# Sensor.net
KiCad netlist of a schematic drawn in EAGLE
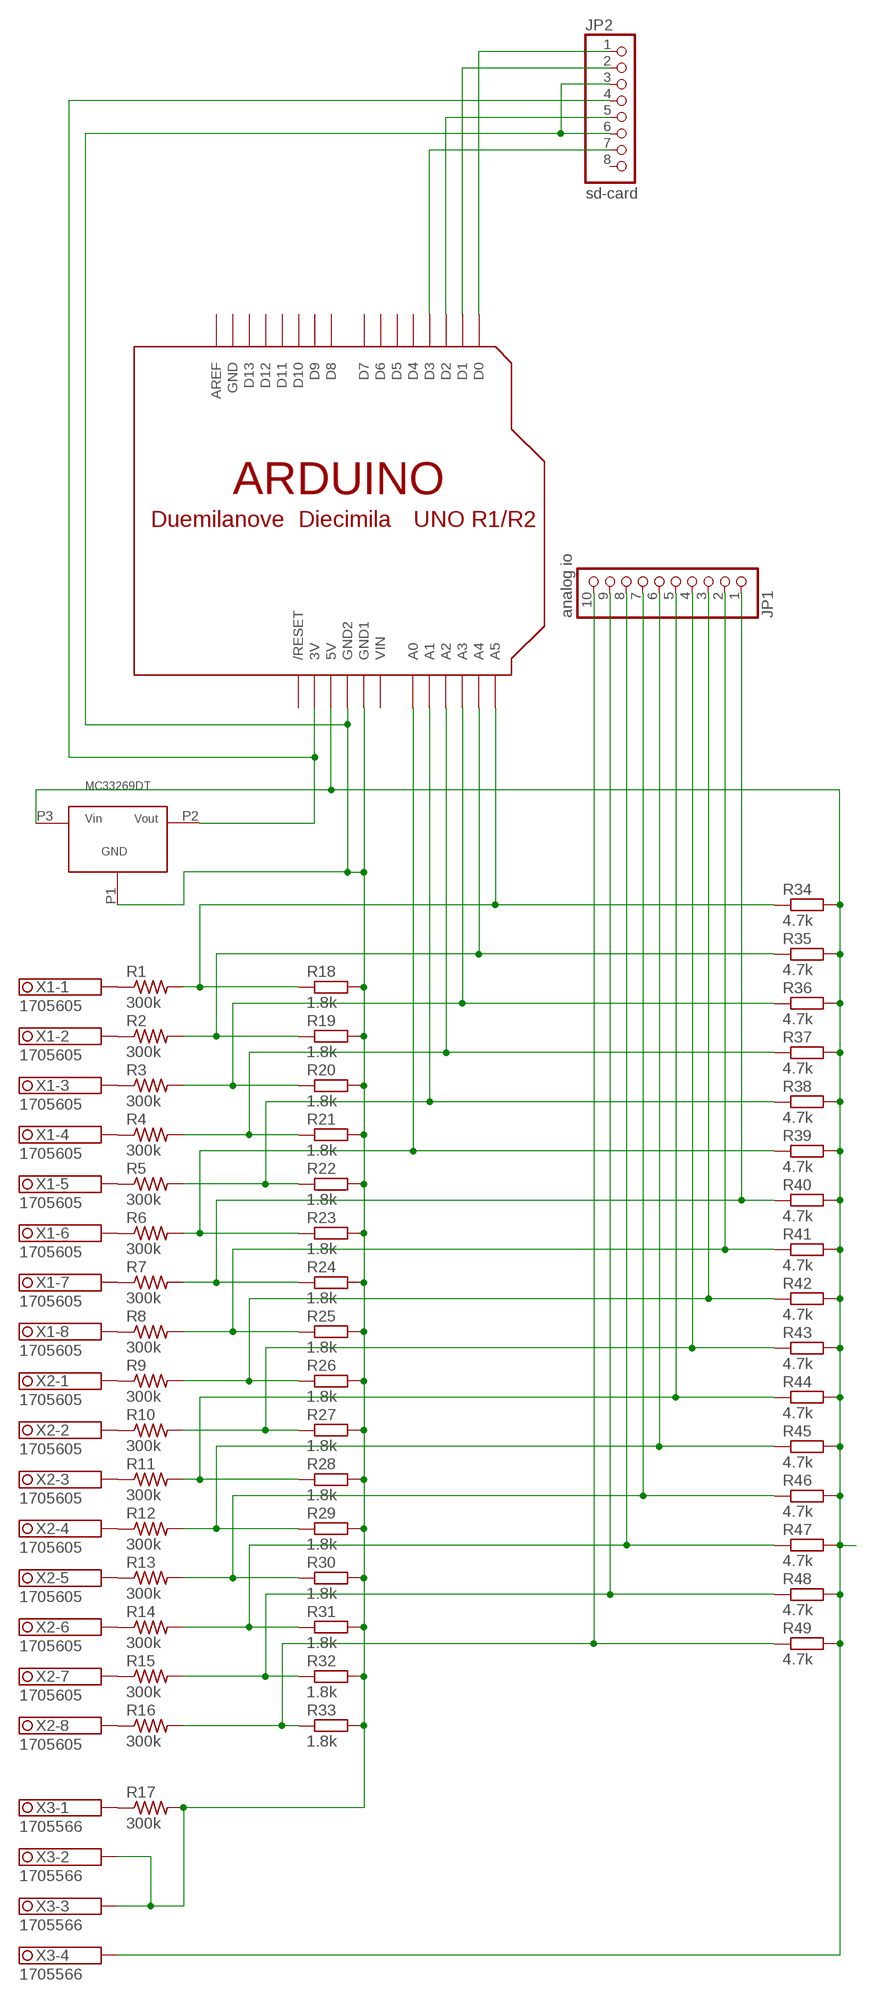
[diagram p0: schematic, sheet 1]

(export (version "E")
  (design (tool "Eeschema 10.0.6"))
  (components
    (comp (ref "JP1")
      (value "analog io")
      (footprint "eagle-import:1X10")
      (libsource (lib "eagle-import") (part "PINHD-1X10"))
    )
    (comp (ref "JP2")
      (value "sd-card")
      (footprint "eagle-import:1X08")
      (libsource (lib "eagle-import") (part "PINHD-1X8"))
    )
    (comp (ref "R1")
      (value "300k")
      (footprint "eagle-import:0207_15")
      (libsource (lib "eagle-import") (part "R-US_0207/15"))
    )
    (comp (ref "R2")
      (value "300k")
      (footprint "eagle-import:0207_15")
      (libsource (lib "eagle-import") (part "R-US_0207/15"))
    )
    (comp (ref "R3")
      (value "300k")
      (footprint "eagle-import:0207_15")
      (libsource (lib "eagle-import") (part "R-US_0207/15"))
    )
    (comp (ref "R4")
      (value "300k")
      (footprint "eagle-import:0207_15")
      (libsource (lib "eagle-import") (part "R-US_0207/15"))
    )
    (comp (ref "R5")
      (value "300k")
      (footprint "eagle-import:0207_15")
      (libsource (lib "eagle-import") (part "R-US_0207/15"))
    )
    (comp (ref "R6")
      (value "300k")
      (footprint "eagle-import:0207_15")
      (libsource (lib "eagle-import") (part "R-US_0207/15"))
    )
    (comp (ref "R7")
      (value "300k")
      (footprint "eagle-import:0207_15")
      (libsource (lib "eagle-import") (part "R-US_0207/15"))
    )
    (comp (ref "R8")
      (value "300k")
      (footprint "eagle-import:0207_15")
      (libsource (lib "eagle-import") (part "R-US_0207/15"))
    )
    (comp (ref "R9")
      (value "300k")
      (footprint "eagle-import:0207_15")
      (libsource (lib "eagle-import") (part "R-US_0207/15"))
    )
    (comp (ref "R10")
      (value "300k")
      (footprint "eagle-import:0207_15")
      (libsource (lib "eagle-import") (part "R-US_0207/15"))
    )
    (comp (ref "R11")
      (value "300k")
      (footprint "eagle-import:0207_15")
      (libsource (lib "eagle-import") (part "R-US_0207/15"))
    )
    (comp (ref "R12")
      (value "300k")
      (footprint "eagle-import:0207_15")
      (libsource (lib "eagle-import") (part "R-US_0207/15"))
    )
    (comp (ref "R13")
      (value "300k")
      (footprint "eagle-import:0207_15")
      (libsource (lib "eagle-import") (part "R-US_0207/15"))
    )
    (comp (ref "R14")
      (value "300k")
      (footprint "eagle-import:0207_15")
      (libsource (lib "eagle-import") (part "R-US_0207/15"))
    )
    (comp (ref "R15")
      (value "300k")
      (footprint "eagle-import:0207_15")
      (libsource (lib "eagle-import") (part "R-US_0207/15"))
    )
    (comp (ref "R16")
      (value "300k")
      (footprint "eagle-import:0207_15")
      (libsource (lib "eagle-import") (part "R-US_0207/15"))
    )
    (comp (ref "R17")
      (value "300k")
      (footprint "eagle-import:0207_15")
      (libsource (lib "eagle-import") (part "R-US_0207/15"))
    )
    (comp (ref "R18")
      (value "1.8k")
      (footprint "eagle-import:R1206")
      (libsource (lib "eagle-import") (part "R-EU_R1206"))
    )
    (comp (ref "R19")
      (value "1.8k")
      (footprint "eagle-import:R1206")
      (libsource (lib "eagle-import") (part "R-EU_R1206"))
    )
    (comp (ref "R20")
      (value "1.8k")
      (footprint "eagle-import:R1206")
      (libsource (lib "eagle-import") (part "R-EU_R1206"))
    )
    (comp (ref "R21")
      (value "1.8k")
      (footprint "eagle-import:R1206")
      (libsource (lib "eagle-import") (part "R-EU_R1206"))
    )
    (comp (ref "R22")
      (value "1.8k")
      (footprint "eagle-import:R1206")
      (libsource (lib "eagle-import") (part "R-EU_R1206"))
    )
    (comp (ref "R23")
      (value "1.8k")
      (footprint "eagle-import:R1206")
      (libsource (lib "eagle-import") (part "R-EU_R1206"))
    )
    (comp (ref "R24")
      (value "1.8k")
      (footprint "eagle-import:R1206")
      (libsource (lib "eagle-import") (part "R-EU_R1206"))
    )
    (comp (ref "R25")
      (value "1.8k")
      (footprint "eagle-import:R1206")
      (libsource (lib "eagle-import") (part "R-EU_R1206"))
    )
    (comp (ref "R26")
      (value "1.8k")
      (footprint "eagle-import:R1206")
      (libsource (lib "eagle-import") (part "R-EU_R1206"))
    )
    (comp (ref "R27")
      (value "1.8k")
      (footprint "eagle-import:R1206")
      (libsource (lib "eagle-import") (part "R-EU_R1206"))
    )
    (comp (ref "R28")
      (value "1.8k")
      (footprint "eagle-import:R1206")
      (libsource (lib "eagle-import") (part "R-EU_R1206"))
    )
    (comp (ref "R29")
      (value "1.8k")
      (footprint "eagle-import:R1206")
      (libsource (lib "eagle-import") (part "R-EU_R1206"))
    )
    (comp (ref "R30")
      (value "1.8k")
      (footprint "eagle-import:R1206")
      (libsource (lib "eagle-import") (part "R-EU_R1206"))
    )
    (comp (ref "R31")
      (value "1.8k")
      (footprint "eagle-import:R1206")
      (libsource (lib "eagle-import") (part "R-EU_R1206"))
    )
    (comp (ref "R32")
      (value "1.8k")
      (footprint "eagle-import:R1206")
      (libsource (lib "eagle-import") (part "R-EU_R1206"))
    )
    (comp (ref "R33")
      (value "1.8k")
      (footprint "eagle-import:R1206")
      (libsource (lib "eagle-import") (part "R-EU_R1206"))
    )
    (comp (ref "R34")
      (value "4.7k")
      (footprint "eagle-import:R1206")
      (libsource (lib "eagle-import") (part "R-EU_R1206"))
    )
    (comp (ref "R35")
      (value "4.7k")
      (footprint "eagle-import:R1206")
      (libsource (lib "eagle-import") (part "R-EU_R1206"))
    )
    (comp (ref "R36")
      (value "4.7k")
      (footprint "eagle-import:R1206")
      (libsource (lib "eagle-import") (part "R-EU_R1206"))
    )
    (comp (ref "R37")
      (value "4.7k")
      (footprint "eagle-import:R1206")
      (libsource (lib "eagle-import") (part "R-EU_R1206"))
    )
    (comp (ref "R38")
      (value "4.7k")
      (footprint "eagle-import:R1206")
      (libsource (lib "eagle-import") (part "R-EU_R1206"))
    )
    (comp (ref "R39")
      (value "4.7k")
      (footprint "eagle-import:R1206")
      (libsource (lib "eagle-import") (part "R-EU_R1206"))
    )
    (comp (ref "R40")
      (value "4.7k")
      (footprint "eagle-import:R1206")
      (libsource (lib "eagle-import") (part "R-EU_R1206"))
    )
    (comp (ref "R41")
      (value "4.7k")
      (footprint "eagle-import:R1206")
      (libsource (lib "eagle-import") (part "R-EU_R1206"))
    )
    (comp (ref "R42")
      (value "4.7k")
      (footprint "eagle-import:R1206")
      (libsource (lib "eagle-import") (part "R-EU_R1206"))
    )
    (comp (ref "R43")
      (value "4.7k")
      (footprint "eagle-import:R1206")
      (libsource (lib "eagle-import") (part "R-EU_R1206"))
    )
    (comp (ref "R44")
      (value "4.7k")
      (footprint "eagle-import:R1206")
      (libsource (lib "eagle-import") (part "R-EU_R1206"))
    )
    (comp (ref "R45")
      (value "4.7k")
      (footprint "eagle-import:R1206")
      (libsource (lib "eagle-import") (part "R-EU_R1206"))
    )
    (comp (ref "R46")
      (value "4.7k")
      (footprint "eagle-import:R1206")
      (libsource (lib "eagle-import") (part "R-EU_R1206"))
    )
    (comp (ref "R47")
      (value "4.7k")
      (footprint "eagle-import:R1206")
      (libsource (lib "eagle-import") (part "R-EU_R1206"))
    )
    (comp (ref "R48")
      (value "4.7k")
      (footprint "eagle-import:R1206")
      (libsource (lib "eagle-import") (part "R-EU_R1206"))
    )
    (comp (ref "R49")
      (value "4.7k")
      (footprint "eagle-import:R1206")
      (libsource (lib "eagle-import") (part "R-EU_R1206"))
    )
    (comp (ref "U$1")
      (value "MC33269DT")
      (footprint "eagle-import:MC33269DT")
      (libsource (lib "eagle-import") (part "MC33269DT"))
    )
    (comp (ref "U$2")
      (value "ARDUINOUNO")
      (footprint "eagle-import:ARDUINO")
      (libsource (lib "eagle-import") (part "ARDUINOUNO"))
    )
    (comp (ref "X1")
      (value "1705605")
      (footprint "eagle-import:1705605")
      (libsource (lib "eagle-import") (part "1705605"))
    )
    (comp (ref "X2")
      (value "1705605")
      (footprint "eagle-import:1705605")
      (libsource (lib "eagle-import") (part "1705605"))
    )
    (comp (ref "X3")
      (value "1705566")
      (footprint "eagle-import:1705566")
      (libsource (lib "eagle-import") (part "1705566"))
    )
  )
  (nets
    (net (code "1") (name "/GND") (class "Default")
      (node (ref "U$2") (pin "GND") (pinfunction "GND_GND") (pintype "power_in"))
    )
    (net (code "2") (name "/VIN") (class "Default")
      (node (ref "U$2") (pin "VIN") (pinfunction "VIN_VIN") (pintype "power_in"))
    )
    (net (code "3") (name "Net-(JP1-Pad1)") (class "Default")
      (node (ref "JP1") (pin "1") (pinfunction "1_1") (pintype "passive"))
      (node (ref "R24") (pin "1") (pinfunction "1_1") (pintype "passive"))
      (node (ref "R40") (pin "1") (pinfunction "1_1") (pintype "passive"))
      (node (ref "R7") (pin "2") (pinfunction "2_2") (pintype "passive"))
    )
    (net (code "4") (name "Net-(JP1-Pad2)") (class "Default")
      (node (ref "JP1") (pin "2") (pinfunction "2_2") (pintype "passive"))
      (node (ref "R25") (pin "1") (pinfunction "1_1") (pintype "passive"))
      (node (ref "R41") (pin "1") (pinfunction "1_1") (pintype "passive"))
      (node (ref "R8") (pin "2") (pinfunction "2_2") (pintype "passive"))
    )
    (net (code "5") (name "Net-(JP1-Pad3)") (class "Default")
      (node (ref "JP1") (pin "3") (pinfunction "3_3") (pintype "passive"))
      (node (ref "R26") (pin "1") (pinfunction "1_1") (pintype "passive"))
      (node (ref "R42") (pin "1") (pinfunction "1_1") (pintype "passive"))
      (node (ref "R9") (pin "2") (pinfunction "2_2") (pintype "passive"))
    )
    (net (code "6") (name "Net-(JP1-Pad4)") (class "Default")
      (node (ref "JP1") (pin "4") (pinfunction "4_4") (pintype "passive"))
      (node (ref "R10") (pin "2") (pinfunction "2_2") (pintype "passive"))
      (node (ref "R27") (pin "1") (pinfunction "1_1") (pintype "passive"))
      (node (ref "R43") (pin "1") (pinfunction "1_1") (pintype "passive"))
    )
    (net (code "7") (name "Net-(JP1-Pad5)") (class "Default")
      (node (ref "JP1") (pin "5") (pinfunction "5_5") (pintype "passive"))
      (node (ref "R11") (pin "2") (pinfunction "2_2") (pintype "passive"))
      (node (ref "R28") (pin "1") (pinfunction "1_1") (pintype "passive"))
      (node (ref "R44") (pin "1") (pinfunction "1_1") (pintype "passive"))
    )
    (net (code "8") (name "Net-(JP1-Pad6)") (class "Default")
      (node (ref "JP1") (pin "6") (pinfunction "6_6") (pintype "passive"))
      (node (ref "R12") (pin "2") (pinfunction "2_2") (pintype "passive"))
      (node (ref "R29") (pin "1") (pinfunction "1_1") (pintype "passive"))
      (node (ref "R45") (pin "1") (pinfunction "1_1") (pintype "passive"))
    )
    (net (code "9") (name "Net-(JP1-Pad7)") (class "Default")
      (node (ref "JP1") (pin "7") (pinfunction "7_7") (pintype "passive"))
      (node (ref "R13") (pin "2") (pinfunction "2_2") (pintype "passive"))
      (node (ref "R30") (pin "1") (pinfunction "1_1") (pintype "passive"))
      (node (ref "R46") (pin "1") (pinfunction "1_1") (pintype "passive"))
    )
    (net (code "10") (name "Net-(JP1-Pad8)") (class "Default")
      (node (ref "JP1") (pin "8") (pinfunction "8_8") (pintype "passive"))
      (node (ref "R14") (pin "2") (pinfunction "2_2") (pintype "passive"))
      (node (ref "R31") (pin "1") (pinfunction "1_1") (pintype "passive"))
      (node (ref "R47") (pin "1") (pinfunction "1_1") (pintype "passive"))
    )
    (net (code "11") (name "Net-(JP1-Pad9)") (class "Default")
      (node (ref "JP1") (pin "9") (pinfunction "9_9") (pintype "passive"))
      (node (ref "R15") (pin "2") (pinfunction "2_2") (pintype "passive"))
      (node (ref "R32") (pin "1") (pinfunction "1_1") (pintype "passive"))
      (node (ref "R48") (pin "1") (pinfunction "1_1") (pintype "passive"))
    )
    (net (code "12") (name "Net-(JP1-Pad10)") (class "Default")
      (node (ref "JP1") (pin "10") (pinfunction "10_10") (pintype "passive"))
      (node (ref "R16") (pin "2") (pinfunction "2_2") (pintype "passive"))
      (node (ref "R33") (pin "1") (pinfunction "1_1") (pintype "passive"))
      (node (ref "R49") (pin "1") (pinfunction "1_1") (pintype "passive"))
    )
    (net (code "13") (name "Net-(JP2-Pad1)") (class "Default")
      (node (ref "JP2") (pin "1") (pinfunction "1_1") (pintype "passive"))
      (node (ref "U$2") (pin "D0") (pinfunction "D0_D0") (pintype "bidirectional"))
    )
    (net (code "14") (name "Net-(JP2-Pad2)") (class "Default")
      (node (ref "JP2") (pin "2") (pinfunction "2_2") (pintype "passive"))
      (node (ref "U$2") (pin "D1") (pinfunction "D1_D1") (pintype "bidirectional"))
    )
    (net (code "15") (name "Net-(JP2-Pad5)") (class "Default")
      (node (ref "JP2") (pin "5") (pinfunction "5_5") (pintype "passive"))
      (node (ref "U$2") (pin "D2") (pinfunction "D2_D2") (pintype "bidirectional"))
    )
    (net (code "16") (name "Net-(JP2-Pad7)") (class "Default")
      (node (ref "JP2") (pin "7") (pinfunction "7_7") (pintype "passive"))
      (node (ref "U$2") (pin "D3") (pinfunction "D3_D3") (pintype "bidirectional"))
    )
    (net (code "17") (name "Net-(R1-Pad1)") (class "Default")
      (node (ref "R1") (pin "1") (pinfunction "1_1") (pintype "passive"))
      (node (ref "X1") (pin "1.1") (pinfunction "1A_1.1") (pintype "passive"))
      (node (ref "X1") (pin "1.2") (pinfunction "1A_1.2") (pintype "passive"))
    )
    (net (code "18") (name "Net-(R1-Pad2)") (class "Default")
      (node (ref "R1") (pin "2") (pinfunction "2_2") (pintype "passive"))
      (node (ref "R18") (pin "1") (pinfunction "1_1") (pintype "passive"))
      (node (ref "R34") (pin "1") (pinfunction "1_1") (pintype "passive"))
      (node (ref "U$2") (pin "A5") (pinfunction "A5_A5") (pintype "bidirectional"))
    )
    (net (code "19") (name "Net-(R2-Pad1)") (class "Default")
      (node (ref "R2") (pin "1") (pinfunction "1_1") (pintype "passive"))
      (node (ref "X1") (pin "2.1") (pinfunction "1A_2.1") (pintype "passive"))
      (node (ref "X1") (pin "2.2") (pinfunction "1A_2.2") (pintype "passive"))
    )
    (net (code "20") (name "Net-(R3-Pad1)") (class "Default")
      (node (ref "R3") (pin "1") (pinfunction "1_1") (pintype "passive"))
      (node (ref "X1") (pin "3.1") (pinfunction "1A_3.1") (pintype "passive"))
      (node (ref "X1") (pin "3.2") (pinfunction "1A_3.2") (pintype "passive"))
    )
    (net (code "21") (name "Net-(R4-Pad1)") (class "Default")
      (node (ref "R4") (pin "1") (pinfunction "1_1") (pintype "passive"))
      (node (ref "X1") (pin "4.1") (pinfunction "1A_4.1") (pintype "passive"))
      (node (ref "X1") (pin "4.2") (pinfunction "1A_4.2") (pintype "passive"))
    )
    (net (code "22") (name "Net-(R5-Pad1)") (class "Default")
      (node (ref "R5") (pin "1") (pinfunction "1_1") (pintype "passive"))
      (node (ref "X1") (pin "5.1") (pinfunction "1A_5.1") (pintype "passive"))
      (node (ref "X1") (pin "5.2") (pinfunction "1A_5.2") (pintype "passive"))
    )
    (net (code "23") (name "Net-(R6-Pad1)") (class "Default")
      (node (ref "R6") (pin "1") (pinfunction "1_1") (pintype "passive"))
      (node (ref "X1") (pin "6.1") (pinfunction "1A_6.1") (pintype "passive"))
      (node (ref "X1") (pin "6.2") (pinfunction "1A_6.2") (pintype "passive"))
    )
    (net (code "24") (name "Net-(R7-Pad1)") (class "Default")
      (node (ref "R7") (pin "1") (pinfunction "1_1") (pintype "passive"))
      (node (ref "X1") (pin "7.1") (pinfunction "1A_7.1") (pintype "passive"))
      (node (ref "X1") (pin "7.2") (pinfunction "1A_7.2") (pintype "passive"))
    )
    (net (code "25") (name "Net-(R8-Pad1)") (class "Default")
      (node (ref "R8") (pin "1") (pinfunction "1_1") (pintype "passive"))
      (node (ref "X1") (pin "8.1") (pinfunction "1A_8.1") (pintype "passive"))
      (node (ref "X1") (pin "8.2") (pinfunction "1A_8.2") (pintype "passive"))
    )
    (net (code "26") (name "Net-(R9-Pad1)") (class "Default")
      (node (ref "R9") (pin "1") (pinfunction "1_1") (pintype "passive"))
      (node (ref "X2") (pin "1.1") (pinfunction "1A_1.1") (pintype "passive"))
      (node (ref "X2") (pin "1.2") (pinfunction "1A_1.2") (pintype "passive"))
    )
    (net (code "27") (name "Net-(R10-Pad1)") (class "Default")
      (node (ref "R10") (pin "1") (pinfunction "1_1") (pintype "passive"))
      (node (ref "X2") (pin "2.1") (pinfunction "1A_2.1") (pintype "passive"))
      (node (ref "X2") (pin "2.2") (pinfunction "1A_2.2") (pintype "passive"))
    )
    (net (code "28") (name "Net-(R11-Pad1)") (class "Default")
      (node (ref "R11") (pin "1") (pinfunction "1_1") (pintype "passive"))
      (node (ref "X2") (pin "3.1") (pinfunction "1A_3.1") (pintype "passive"))
      (node (ref "X2") (pin "3.2") (pinfunction "1A_3.2") (pintype "passive"))
    )
    (net (code "29") (name "Net-(R12-Pad1)") (class "Default")
      (node (ref "R12") (pin "1") (pinfunction "1_1") (pintype "passive"))
      (node (ref "X2") (pin "4.1") (pinfunction "1A_4.1") (pintype "passive"))
      (node (ref "X2") (pin "4.2") (pinfunction "1A_4.2") (pintype "passive"))
    )
    (net (code "30") (name "Net-(R13-Pad1)") (class "Default")
      (node (ref "R13") (pin "1") (pinfunction "1_1") (pintype "passive"))
      (node (ref "X2") (pin "5.1") (pinfunction "1A_5.1") (pintype "passive"))
      (node (ref "X2") (pin "5.2") (pinfunction "1A_5.2") (pintype "passive"))
    )
    (net (code "31") (name "Net-(R14-Pad1)") (class "Default")
      (node (ref "R14") (pin "1") (pinfunction "1_1") (pintype "passive"))
      (node (ref "X2") (pin "6.1") (pinfunction "1A_6.1") (pintype "passive"))
      (node (ref "X2") (pin "6.2") (pinfunction "1A_6.2") (pintype "passive"))
    )
    (net (code "32") (name "Net-(R15-Pad1)") (class "Default")
      (node (ref "R15") (pin "1") (pinfunction "1_1") (pintype "passive"))
      (node (ref "X2") (pin "7.1") (pinfunction "1A_7.1") (pintype "passive"))
      (node (ref "X2") (pin "7.2") (pinfunction "1A_7.2") (pintype "passive"))
    )
    (net (code "33") (name "Net-(R16-Pad1)") (class "Default")
      (node (ref "R16") (pin "1") (pinfunction "1_1") (pintype "passive"))
      (node (ref "X2") (pin "8.1") (pinfunction "1A_8.1") (pintype "passive"))
      (node (ref "X2") (pin "8.2") (pinfunction "1A_8.2") (pintype "passive"))
    )
    (net (code "34") (name "Net-(R17-Pad1)") (class "Default")
      (node (ref "R17") (pin "1") (pinfunction "1_1") (pintype "passive"))
      (node (ref "X3") (pin "1.1") (pinfunction "1A_1.1") (pintype "passive"))
      (node (ref "X3") (pin "1.2") (pinfunction "1A_1.2") (pintype "passive"))
    )
    (net (code "35") (name "Net-(R19-Pad1)") (class "Default")
      (node (ref "R19") (pin "1") (pinfunction "1_1") (pintype "passive"))
      (node (ref "R2") (pin "2") (pinfunction "2_2") (pintype "passive"))
      (node (ref "R35") (pin "1") (pinfunction "1_1") (pintype "passive"))
      (node (ref "U$2") (pin "A4") (pinfunction "A4_A4") (pintype "bidirectional"))
    )
    (net (code "36") (name "Net-(R20-Pad1)") (class "Default")
      (node (ref "R20") (pin "1") (pinfunction "1_1") (pintype "passive"))
      (node (ref "R3") (pin "2") (pinfunction "2_2") (pintype "passive"))
      (node (ref "R36") (pin "1") (pinfunction "1_1") (pintype "passive"))
      (node (ref "U$2") (pin "A3") (pinfunction "A3_A3") (pintype "bidirectional"))
    )
    (net (code "37") (name "Net-(R21-Pad1)") (class "Default")
      (node (ref "R21") (pin "1") (pinfunction "1_1") (pintype "passive"))
      (node (ref "R37") (pin "1") (pinfunction "1_1") (pintype "passive"))
      (node (ref "R4") (pin "2") (pinfunction "2_2") (pintype "passive"))
      (node (ref "U$2") (pin "A2") (pinfunction "A2_A2") (pintype "bidirectional"))
    )
    (net (code "38") (name "Net-(R22-Pad1)") (class "Default")
      (node (ref "R22") (pin "1") (pinfunction "1_1") (pintype "passive"))
      (node (ref "R38") (pin "1") (pinfunction "1_1") (pintype "passive"))
      (node (ref "R5") (pin "2") (pinfunction "2_2") (pintype "passive"))
      (node (ref "U$2") (pin "A1") (pinfunction "A1_A1") (pintype "bidirectional"))
    )
    (net (code "39") (name "Net-(R23-Pad1)") (class "Default")
      (node (ref "R23") (pin "1") (pinfunction "1_1") (pintype "passive"))
      (node (ref "R39") (pin "1") (pinfunction "1_1") (pintype "passive"))
      (node (ref "R6") (pin "2") (pinfunction "2_2") (pintype "passive"))
      (node (ref "U$2") (pin "A0") (pinfunction "A0_A0") (pintype "bidirectional"))
    )
    (net (code "40") (name "Net-(U$1-GND)") (class "Default")
      (node (ref "JP2") (pin "3") (pinfunction "3_3") (pintype "passive"))
      (node (ref "JP2") (pin "6") (pinfunction "6_6") (pintype "passive"))
      (node (ref "R17") (pin "2") (pinfunction "2_2") (pintype "passive"))
      (node (ref "R18") (pin "2") (pinfunction "2_2") (pintype "passive"))
      (node (ref "R19") (pin "2") (pinfunction "2_2") (pintype "passive"))
      (node (ref "R20") (pin "2") (pinfunction "2_2") (pintype "passive"))
      (node (ref "R21") (pin "2") (pinfunction "2_2") (pintype "passive"))
      (node (ref "R22") (pin "2") (pinfunction "2_2") (pintype "passive"))
      (node (ref "R23") (pin "2") (pinfunction "2_2") (pintype "passive"))
      (node (ref "R24") (pin "2") (pinfunction "2_2") (pintype "passive"))
      (node (ref "R25") (pin "2") (pinfunction "2_2") (pintype "passive"))
      (node (ref "R26") (pin "2") (pinfunction "2_2") (pintype "passive"))
      (node (ref "R27") (pin "2") (pinfunction "2_2") (pintype "passive"))
      (node (ref "R28") (pin "2") (pinfunction "2_2") (pintype "passive"))
      (node (ref "R29") (pin "2") (pinfunction "2_2") (pintype "passive"))
      (node (ref "R30") (pin "2") (pinfunction "2_2") (pintype "passive"))
      (node (ref "R31") (pin "2") (pinfunction "2_2") (pintype "passive"))
      (node (ref "R32") (pin "2") (pinfunction "2_2") (pintype "passive"))
      (node (ref "R33") (pin "2") (pinfunction "2_2") (pintype "passive"))
      (node (ref "U$1") (pin "P1") (pinfunction "GND_P1") (pintype "power_in"))
      (node (ref "U$2") (pin "GND1") (pinfunction "GND1_GND1") (pintype "power_in"))
      (node (ref "U$2") (pin "GND2") (pinfunction "GND2_GND2") (pintype "power_in"))
      (node (ref "X3") (pin "2.1") (pinfunction "1A_2.1") (pintype "passive"))
      (node (ref "X3") (pin "2.2") (pinfunction "1A_2.2") (pintype "passive"))
      (node (ref "X3") (pin "3.1") (pinfunction "1A_3.1") (pintype "passive"))
      (node (ref "X3") (pin "3.2") (pinfunction "1A_3.2") (pintype "passive"))
    )
    (net (code "41") (name "Net-(U$1-VIN)") (class "Default")
      (node (ref "R34") (pin "2") (pinfunction "2_2") (pintype "passive"))
      (node (ref "R35") (pin "2") (pinfunction "2_2") (pintype "passive"))
      (node (ref "R36") (pin "2") (pinfunction "2_2") (pintype "passive"))
      (node (ref "R37") (pin "2") (pinfunction "2_2") (pintype "passive"))
      (node (ref "R38") (pin "2") (pinfunction "2_2") (pintype "passive"))
      (node (ref "R39") (pin "2") (pinfunction "2_2") (pintype "passive"))
      (node (ref "R40") (pin "2") (pinfunction "2_2") (pintype "passive"))
      (node (ref "R41") (pin "2") (pinfunction "2_2") (pintype "passive"))
      (node (ref "R42") (pin "2") (pinfunction "2_2") (pintype "passive"))
      (node (ref "R43") (pin "2") (pinfunction "2_2") (pintype "passive"))
      (node (ref "R44") (pin "2") (pinfunction "2_2") (pintype "passive"))
      (node (ref "R45") (pin "2") (pinfunction "2_2") (pintype "passive"))
      (node (ref "R46") (pin "2") (pinfunction "2_2") (pintype "passive"))
      (node (ref "R47") (pin "2") (pinfunction "2_2") (pintype "passive"))
      (node (ref "R48") (pin "2") (pinfunction "2_2") (pintype "passive"))
      (node (ref "R49") (pin "2") (pinfunction "2_2") (pintype "passive"))
      (node (ref "U$1") (pin "P3") (pinfunction "VIN_P3") (pintype "input"))
      (node (ref "U$2") (pin "5V") (pinfunction "5V_5V") (pintype "power_in"))
      (node (ref "X3") (pin "4.1") (pinfunction "1A_4.1") (pintype "passive"))
      (node (ref "X3") (pin "4.2") (pinfunction "1A_4.2") (pintype "passive"))
    )
    (net (code "42") (name "Net-(U$1-VOUT)") (class "Default")
      (node (ref "JP2") (pin "4") (pinfunction "4_4") (pintype "passive"))
      (node (ref "U$1") (pin "P2") (pinfunction "VOUT_P2") (pintype "output"))
      (node (ref "U$2") (pin "3V") (pinfunction "3V_3V") (pintype "power_in"))
    )
    (net (code "43") (name "unconnected-(JP2-Pad8)") (class "Default")
      (node (ref "JP2") (pin "8") (pinfunction "8_8") (pintype "passive"))
    )
    (net (code "44") (name "unconnected-(U$2-PadAREF)") (class "Default")
      (node (ref "U$2") (pin "AREF") (pinfunction "AREF_AREF") (pintype "bidirectional"))
    )
    (net (code "45") (name "unconnected-(U$2-PadD4)") (class "Default")
      (node (ref "U$2") (pin "D4") (pinfunction "D4_D4") (pintype "bidirectional"))
    )
    (net (code "46") (name "unconnected-(U$2-PadD5)") (class "Default")
      (node (ref "U$2") (pin "D5") (pinfunction "D5_D5") (pintype "bidirectional"))
    )
    (net (code "47") (name "unconnected-(U$2-PadD6)") (class "Default")
      (node (ref "U$2") (pin "D6") (pinfunction "D6_D6") (pintype "bidirectional"))
    )
    (net (code "48") (name "unconnected-(U$2-PadD7)") (class "Default")
      (node (ref "U$2") (pin "D7") (pinfunction "D7_D7") (pintype "bidirectional"))
    )
    (net (code "49") (name "unconnected-(U$2-PadD8)") (class "Default")
      (node (ref "U$2") (pin "D8") (pinfunction "D8_D8") (pintype "bidirectional"))
    )
    (net (code "50") (name "unconnected-(U$2-PadD9)") (class "Default")
      (node (ref "U$2") (pin "D9") (pinfunction "D9_D9") (pintype "bidirectional"))
    )
    (net (code "51") (name "unconnected-(U$2-PadD10)") (class "Default")
      (node (ref "U$2") (pin "D10") (pinfunction "D10_D10") (pintype "bidirectional"))
    )
    (net (code "52") (name "unconnected-(U$2-PadD11)") (class "Default")
      (node (ref "U$2") (pin "D11") (pinfunction "D11_D11") (pintype "bidirectional"))
    )
    (net (code "53") (name "unconnected-(U$2-PadD12)") (class "Default")
      (node (ref "U$2") (pin "D12") (pinfunction "D12_D12") (pintype "bidirectional"))
    )
    (net (code "54") (name "unconnected-(U$2-PadD13)") (class "Default")
      (node (ref "U$2") (pin "D13") (pinfunction "D13_D13") (pintype "bidirectional"))
    )
    (net (code "55") (name "unconnected-(U$2-{slash}RESET-PadRESET)") (class "Default")
      (node (ref "U$2") (pin "RESET") (pinfunction "/RESET_RESET") (pintype "bidirectional"))
    )
  )
)
